# 05_MOTORS.net
KiCad netlist of a schematic drawn in Altium Designer
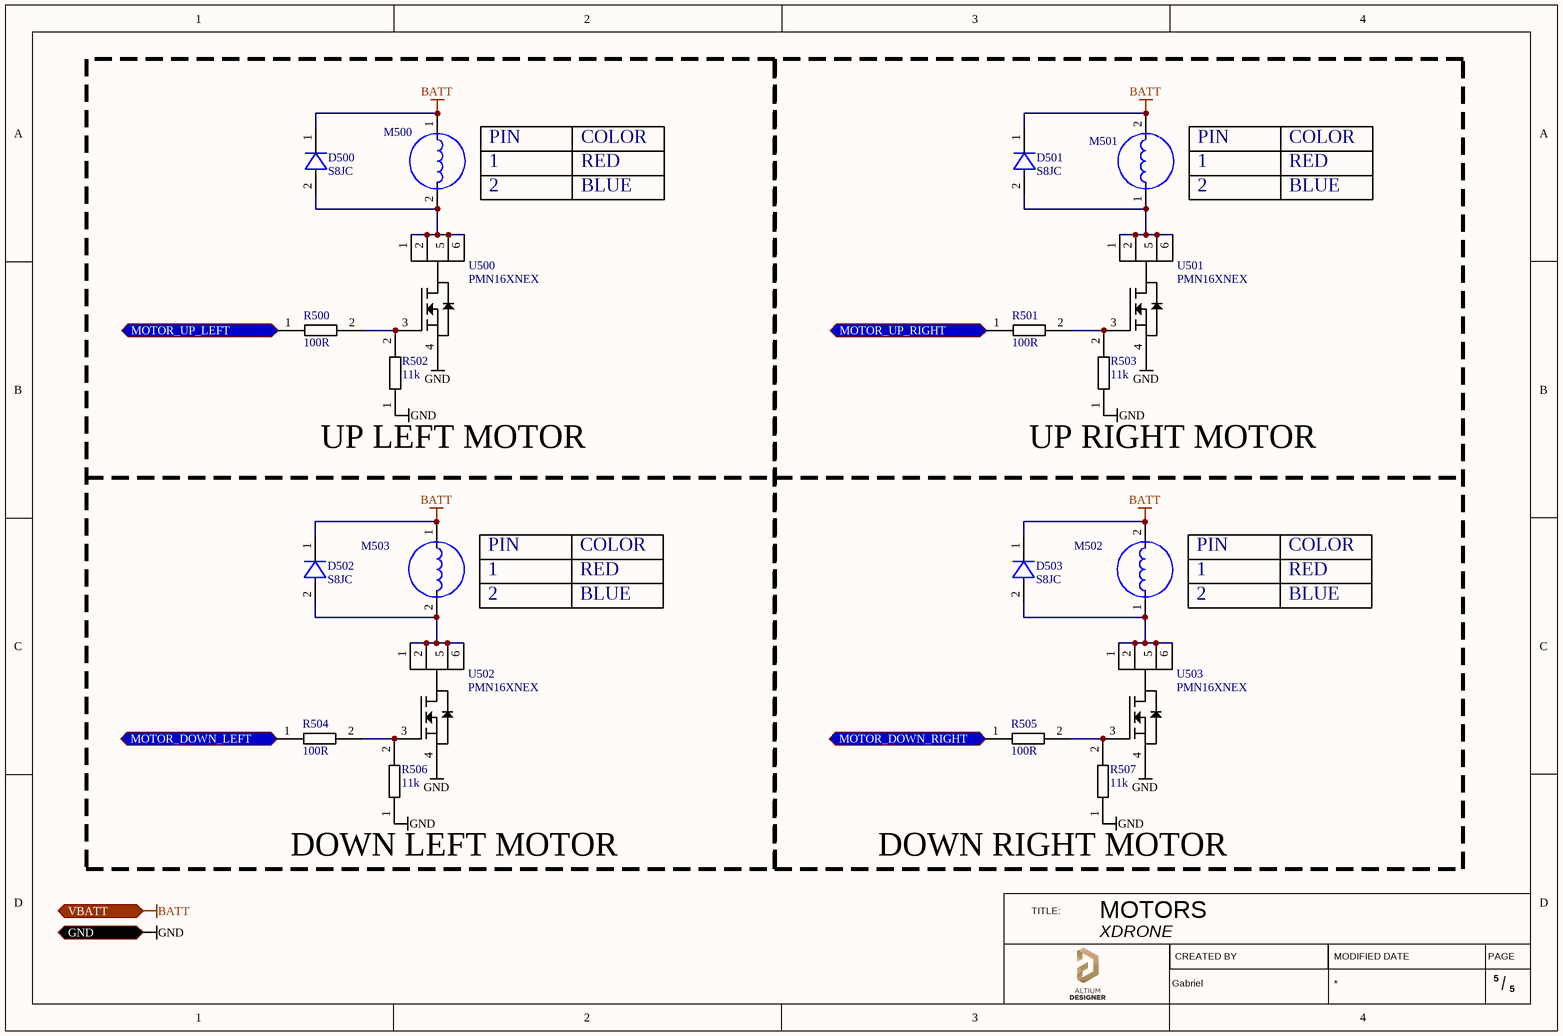
[diagram p0: 05_MOTORS.SchDoc]

(export (version "E")
  (design (tool "Eeschema 10.0.6"))
  (components
    (comp (ref "D500")
      (value "DIODE_600V_8A_1Vf_S8JC")
      (description "DIODE 600V 8A 1Vf S8JC")
      (fields (field (name "MANUFACTURER") "TAIWAN") (field (name "MANUFACTURER REFERENCE") "S8JC"))
      (libsource (lib "Semiconductor") (part "DIODE_600V_8A_1Vf_S8JC"))
    )
    (comp (ref "D501")
      (value "DIODE_600V_8A_1Vf_S8JC")
      (description "DIODE 600V 8A 1Vf S8JC")
      (fields (field (name "MANUFACTURER") "TAIWAN") (field (name "MANUFACTURER REFERENCE") "S8JC"))
      (libsource (lib "Semiconductor") (part "DIODE_600V_8A_1Vf_S8JC"))
    )
    (comp (ref "D502")
      (value "DIODE_600V_8A_1Vf_S8JC")
      (description "DIODE 600V 8A 1Vf S8JC")
      (fields (field (name "MANUFACTURER") "TAIWAN") (field (name "MANUFACTURER REFERENCE") "S8JC"))
      (libsource (lib "Semiconductor") (part "DIODE_600V_8A_1Vf_S8JC"))
    )
    (comp (ref "D503")
      (value "DIODE_600V_8A_1Vf_S8JC")
      (description "DIODE 600V 8A 1Vf S8JC")
      (fields (field (name "MANUFACTURER") "TAIWAN") (field (name "MANUFACTURER REFERENCE") "S8JC"))
      (libsource (lib "Semiconductor") (part "DIODE_600V_8A_1Vf_S8JC"))
    )
    (comp (ref "M500")
      (value "BDC_1020_3.7V_4A")
      (description "Brushed DC motor 3.7V")
      (fields (field (name "MANUFACTURER") "Aliexpress"))
      (libsource (lib "Motors") (part "BDC_1020_3.7V_4A"))
    )
    (comp (ref "M501")
      (value "BDC_1020_3.7V_4A")
      (description "Brushed DC motor 3.7V")
      (fields (field (name "MANUFACTURER") "Aliexpress"))
      (libsource (lib "Motors") (part "BDC_1020_3.7V_4A"))
    )
    (comp (ref "M502")
      (value "BDC_1020_3.7V_4A")
      (description "Brushed DC motor 3.7V")
      (fields (field (name "MANUFACTURER") "Aliexpress"))
      (libsource (lib "Motors") (part "BDC_1020_3.7V_4A"))
    )
    (comp (ref "M503")
      (value "BDC_1020_3.7V_4A")
      (description "Brushed DC motor 3.7V")
      (fields (field (name "MANUFACTURER") "Aliexpress"))
      (libsource (lib "Motors") (part "BDC_1020_3.7V_4A"))
    )
    (comp (ref "R500")
      (value "100R")
      (footprint "RES_0402")
      (description "RESISTOR 100R 1% 0402 RC0402FR-07100RL")
      (fields (field (name "TOLERANCE") "1%") (field (name "MANUFACTURER") "YAGEO"))
      (libsource (lib "Resistors") (part "RES_100R_1%_0402_RC0402FR-07100RL"))
    )
    (comp (ref "R501")
      (value "100R")
      (footprint "RES_0402")
      (description "RESISTOR 100R 1% 0402 RC0402FR-07100RL")
      (fields (field (name "TOLERANCE") "1%") (field (name "MANUFACTURER") "YAGEO"))
      (libsource (lib "Resistors") (part "RES_100R_1%_0402_RC0402FR-07100RL"))
    )
    (comp (ref "R502")
      (value "11k")
      (footprint "RES_0402")
      (description "RESISTOR 11k 5% 0402 ERJ-2GEJ113X")
      (fields (field (name "TOLERANCE") "5%") (field (name "MANUFACTURER") "PANASONIC"))
      (libsource (lib "Resistors") (part "RES_11k_5%_0402_ERJ-2GEJ113X"))
    )
    (comp (ref "R503")
      (value "11k")
      (footprint "RES_0402")
      (description "RESISTOR 11k 5% 0402 ERJ-2GEJ113X")
      (fields (field (name "TOLERANCE") "5%") (field (name "MANUFACTURER") "PANASONIC"))
      (libsource (lib "Resistors") (part "RES_11k_5%_0402_ERJ-2GEJ113X"))
    )
    (comp (ref "R504")
      (value "100R")
      (footprint "RES_0402")
      (description "RESISTOR 100R 1% 0402 RC0402FR-07100RL")
      (fields (field (name "TOLERANCE") "1%") (field (name "MANUFACTURER") "YAGEO"))
      (libsource (lib "Resistors") (part "RES_100R_1%_0402_RC0402FR-07100RL"))
    )
    (comp (ref "R505")
      (value "100R")
      (footprint "RES_0402")
      (description "RESISTOR 100R 1% 0402 RC0402FR-07100RL")
      (fields (field (name "TOLERANCE") "1%") (field (name "MANUFACTURER") "YAGEO"))
      (libsource (lib "Resistors") (part "RES_100R_1%_0402_RC0402FR-07100RL"))
    )
    (comp (ref "R506")
      (value "11k")
      (footprint "RES_0402")
      (description "RESISTOR 11k 5% 0402 ERJ-2GEJ113X")
      (fields (field (name "TOLERANCE") "5%") (field (name "MANUFACTURER") "PANASONIC"))
      (libsource (lib "Resistors") (part "RES_11k_5%_0402_ERJ-2GEJ113X"))
    )
    (comp (ref "R507")
      (value "11k")
      (footprint "RES_0402")
      (description "RESISTOR 11k 5% 0402 ERJ-2GEJ113X")
      (fields (field (name "TOLERANCE") "5%") (field (name "MANUFACTURER") "PANASONIC"))
      (libsource (lib "Resistors") (part "RES_11k_5%_0402_ERJ-2GEJ113X"))
    )
    (comp (ref "U500")
      (value "MOS_N_1G_20VDS_6.9A_0.65Vth_PMN16XNEX")
      (description "MOS N 1G 20VDS 6.9A 0.65Vth PMN16XNEX")
      (fields (field (name "MANUFACTURER") "NEXPERIA") (field (name "MANUFACTURER REFERENCE") "PMN16XNEX"))
      (libsource (lib "Semiconductor") (part "MOS_N_1G_20VDS_6.9A_0.65Vth_PMN16XNEX"))
    )
    (comp (ref "U501")
      (value "MOS_N_1G_20VDS_6.9A_0.65Vth_PMN16XNEX")
      (description "MOS N 1G 20VDS 6.9A 0.65Vth PMN16XNEX")
      (fields (field (name "MANUFACTURER") "NEXPERIA") (field (name "MANUFACTURER REFERENCE") "PMN16XNEX"))
      (libsource (lib "Semiconductor") (part "MOS_N_1G_20VDS_6.9A_0.65Vth_PMN16XNEX"))
    )
    (comp (ref "U502")
      (value "MOS_N_1G_20VDS_6.9A_0.65Vth_PMN16XNEX")
      (description "MOS N 1G 20VDS 6.9A 0.65Vth PMN16XNEX")
      (fields (field (name "MANUFACTURER") "NEXPERIA") (field (name "MANUFACTURER REFERENCE") "PMN16XNEX"))
      (libsource (lib "Semiconductor") (part "MOS_N_1G_20VDS_6.9A_0.65Vth_PMN16XNEX"))
    )
    (comp (ref "U503")
      (value "MOS_N_1G_20VDS_6.9A_0.65Vth_PMN16XNEX")
      (description "MOS N 1G 20VDS 6.9A 0.65Vth PMN16XNEX")
      (fields (field (name "MANUFACTURER") "NEXPERIA") (field (name "MANUFACTURER REFERENCE") "PMN16XNEX"))
      (libsource (lib "Semiconductor") (part "MOS_N_1G_20VDS_6.9A_0.65Vth_PMN16XNEX"))
    )
  )
  (nets
    (net (code "1") (name "/MOTOR_DOWN_LEFT") (class "Default")
      (node (ref "R504") (pin "1") (pinfunction "1_1") (pintype "passive"))
    )
    (net (code "2") (name "/MOTOR_DOWN_RIGHT") (class "Default")
      (node (ref "R505") (pin "1") (pinfunction "1_1") (pintype "passive"))
    )
    (net (code "3") (name "/MOTOR_UP_LEFT") (class "Default")
      (node (ref "R500") (pin "1") (pinfunction "1_1") (pintype "passive"))
    )
    (net (code "4") (name "/MOTOR_UP_RIGHT") (class "Default")
      (node (ref "R501") (pin "1") (pinfunction "1_1") (pintype "passive"))
    )
    (net (code "5") (name "BATT") (class "Default")
      (node (ref "D500") (pin "1") (pinfunction "1_1") (pintype "passive"))
      (node (ref "D501") (pin "1") (pinfunction "1_1") (pintype "passive"))
      (node (ref "D502") (pin "1") (pinfunction "1_1") (pintype "passive"))
      (node (ref "D503") (pin "1") (pinfunction "1_1") (pintype "passive"))
      (node (ref "M500") (pin "1") (pinfunction "1_1") (pintype "passive"))
      (node (ref "M501") (pin "2") (pinfunction "2_2") (pintype "passive"))
      (node (ref "M502") (pin "2") (pinfunction "2_2") (pintype "passive"))
      (node (ref "M503") (pin "1") (pinfunction "1_1") (pintype "passive"))
    )
    (net (code "6") (name "GND") (class "Default")
      (node (ref "R502") (pin "1") (pinfunction "1_1") (pintype "passive"))
      (node (ref "R503") (pin "1") (pinfunction "1_1") (pintype "passive"))
      (node (ref "R506") (pin "1") (pinfunction "1_1") (pintype "passive"))
      (node (ref "R507") (pin "1") (pinfunction "1_1") (pintype "passive"))
      (node (ref "U500") (pin "4") (pinfunction "4_4") (pintype "passive"))
      (node (ref "U501") (pin "4") (pinfunction "4_4") (pintype "passive"))
      (node (ref "U502") (pin "4") (pinfunction "4_4") (pintype "passive"))
      (node (ref "U503") (pin "4") (pinfunction "4_4") (pintype "passive"))
    )
    (net (code "7") (name "Net-(D500-Pad2)") (class "Default")
      (node (ref "D500") (pin "2") (pinfunction "2_2") (pintype "passive"))
      (node (ref "M500") (pin "2") (pinfunction "2_2") (pintype "passive"))
      (node (ref "U500") (pin "1") (pinfunction "1_1") (pintype "passive"))
      (node (ref "U500") (pin "2") (pinfunction "2_2") (pintype "passive"))
      (node (ref "U500") (pin "5") (pinfunction "5_5") (pintype "passive"))
      (node (ref "U500") (pin "6") (pinfunction "6_6") (pintype "passive"))
    )
    (net (code "8") (name "Net-(D501-Pad2)") (class "Default")
      (node (ref "D501") (pin "2") (pinfunction "2_2") (pintype "passive"))
      (node (ref "M501") (pin "1") (pinfunction "1_1") (pintype "passive"))
      (node (ref "U501") (pin "1") (pinfunction "1_1") (pintype "passive"))
      (node (ref "U501") (pin "2") (pinfunction "2_2") (pintype "passive"))
      (node (ref "U501") (pin "5") (pinfunction "5_5") (pintype "passive"))
      (node (ref "U501") (pin "6") (pinfunction "6_6") (pintype "passive"))
    )
    (net (code "9") (name "Net-(D502-Pad2)") (class "Default")
      (node (ref "D502") (pin "2") (pinfunction "2_2") (pintype "passive"))
      (node (ref "M503") (pin "2") (pinfunction "2_2") (pintype "passive"))
      (node (ref "U502") (pin "1") (pinfunction "1_1") (pintype "passive"))
      (node (ref "U502") (pin "2") (pinfunction "2_2") (pintype "passive"))
      (node (ref "U502") (pin "5") (pinfunction "5_5") (pintype "passive"))
      (node (ref "U502") (pin "6") (pinfunction "6_6") (pintype "passive"))
    )
    (net (code "10") (name "Net-(D503-Pad2)") (class "Default")
      (node (ref "D503") (pin "2") (pinfunction "2_2") (pintype "passive"))
      (node (ref "M502") (pin "1") (pinfunction "1_1") (pintype "passive"))
      (node (ref "U503") (pin "1") (pinfunction "1_1") (pintype "passive"))
      (node (ref "U503") (pin "2") (pinfunction "2_2") (pintype "passive"))
      (node (ref "U503") (pin "5") (pinfunction "5_5") (pintype "passive"))
      (node (ref "U503") (pin "6") (pinfunction "6_6") (pintype "passive"))
    )
    (net (code "11") (name "Net-(R500-Pad2)") (class "Default")
      (node (ref "R500") (pin "2") (pinfunction "2_2") (pintype "passive"))
      (node (ref "R502") (pin "2") (pinfunction "2_2") (pintype "passive"))
      (node (ref "U500") (pin "3") (pinfunction "3_3") (pintype "passive"))
    )
    (net (code "12") (name "Net-(R501-Pad2)") (class "Default")
      (node (ref "R501") (pin "2") (pinfunction "2_2") (pintype "passive"))
      (node (ref "R503") (pin "2") (pinfunction "2_2") (pintype "passive"))
      (node (ref "U501") (pin "3") (pinfunction "3_3") (pintype "passive"))
    )
    (net (code "13") (name "Net-(R504-Pad2)") (class "Default")
      (node (ref "R504") (pin "2") (pinfunction "2_2") (pintype "passive"))
      (node (ref "R506") (pin "2") (pinfunction "2_2") (pintype "passive"))
      (node (ref "U502") (pin "3") (pinfunction "3_3") (pintype "passive"))
    )
    (net (code "14") (name "Net-(R505-Pad2)") (class "Default")
      (node (ref "R505") (pin "2") (pinfunction "2_2") (pintype "passive"))
      (node (ref "R507") (pin "2") (pinfunction "2_2") (pintype "passive"))
      (node (ref "U503") (pin "3") (pinfunction "3_3") (pintype "passive"))
    )
  )
)
